# 10cm-chip-cal-board-1point2in.net
KiCad netlist of a schematic drawn in Altium Designer
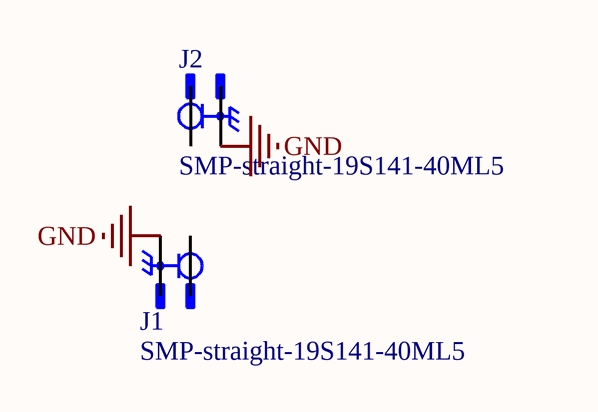
[diagram p0: 10cm-chip-cal-board-1point2in.SchDoc]

(export (version "E")
  (design (tool "Eeschema 10.0.6"))
  (components
    (comp (ref "J1")
      (value "SMP-straight-19S141-40ML5")
      (footprint "rosenberger-19S141-40ML5")
      (description "SMP Connector Plug, Male Pin 50Ohm Surface Mount Solder")
      (fields (field (name "MP") "853050232") (field (name "MF") "Molex"))
      (libsource (lib "") (part "SMP-straight-19S141-40ML5_1"))
    )
    (comp (ref "J2")
      (value "SMP-straight-19S141-40ML5")
      (footprint "rosenberger-19S141-40ML5")
      (description "SMP Connector Plug, Male Pin 50Ohm Surface Mount Solder")
      (fields (field (name "MP") "853050232") (field (name "MF") "Molex"))
      (libsource (lib "SchlibLafe") (part "SMP-straight-19S141-40ML5"))
    )
  )
  (nets
    (net (code "1") (name "GND") (class "Default")
      (node (ref "J1") (pin "gnd") (pinfunction "gnd_gnd") (pintype "passive"))
      (node (ref "J2") (pin "gnd") (pinfunction "gnd_gnd") (pintype "passive"))
    )
    (net (code "2") (name "unconnected-(J1-Pad1)") (class "Default")
      (node (ref "J1") (pin "1") (pinfunction "1_1") (pintype "passive"))
    )
    (net (code "3") (name "unconnected-(J2-Pad1)") (class "Default")
      (node (ref "J2") (pin "1") (pinfunction "1_1") (pintype "passive"))
    )
  )
)
